# Main.net
KiCad netlist of a schematic drawn in Altium Designer
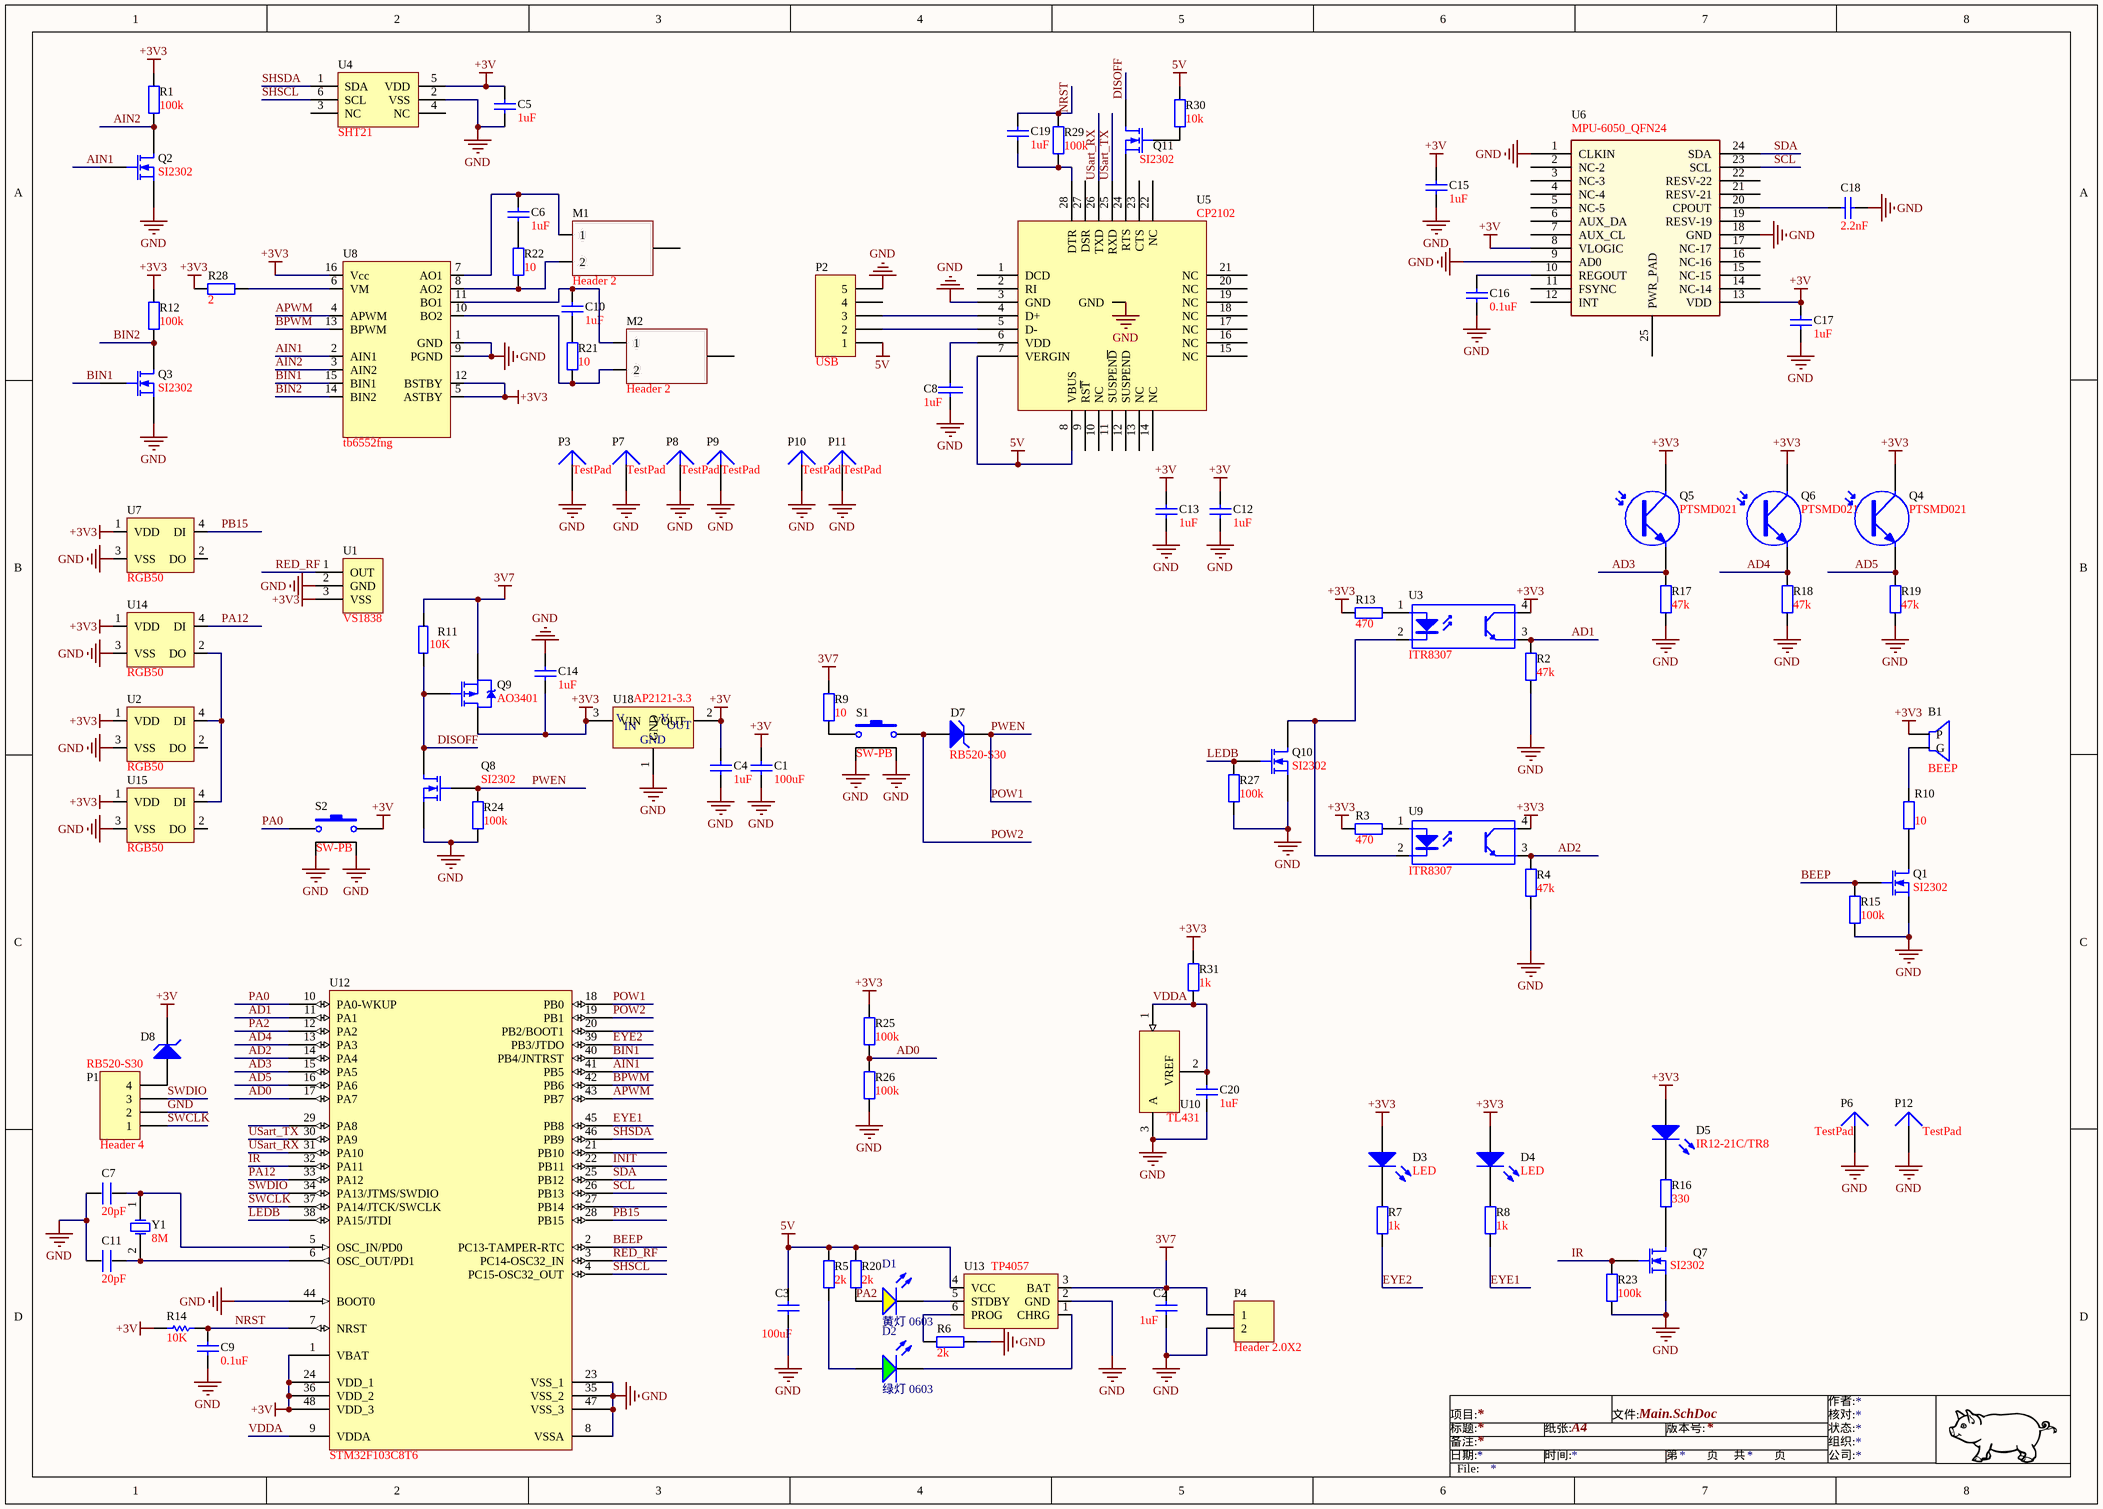
[diagram p0: Main.SchDoc]

(export (version "E")
  (design (tool "Eeschema 10.0.6"))
  (components
    (comp (ref "B1")
      (value "BEEP")
      (footprint "BEEP")
      (description "最小蜂鸣器6MM 6038 6035电磁式蜂鸣器 6*3.5 6*3.8MM 无源 交流")
      (libsource (lib "WARSHIP_SCH") (part "BEEP"))
    )
    (comp (ref "C1")
      (value "100uF")
      (footprint "3.5X2.8X1.9")
      (description "贴片电容")
      (fields (field (name "PUBLISHER") "Altium Limited"))
      (libsource (lib "Miscellaneous Devices") (part "Cap"))
    )
    (comp (ref "C2")
      (value "1uF")
      (footprint "C0603")
      (description "贴片电容")
      (fields (field (name "PUBLISHER") "Altium Limited"))
      (libsource (lib "Miscellaneous Devices") (part "Cap"))
    )
    (comp (ref "C3")
      (value "100uF")
      (footprint "3.5X2.8X1.9")
      (description "贴片电容")
      (fields (field (name "PUBLISHER") "Altium Limited"))
      (libsource (lib "Miscellaneous Devices") (part "Cap"))
    )
    (comp (ref "C4")
      (value "1uF")
      (footprint "C0603")
      (description "贴片电容")
      (fields (field (name "PUBLISHER") "Altium Limited"))
      (libsource (lib "Miscellaneous Devices") (part "Cap"))
    )
    (comp (ref "C5")
      (value "1uF")
      (footprint "c0603")
      (description "贴片电容")
      (fields (field (name "PUBLISHER") "Altium Limited"))
      (libsource (lib "Miscellaneous Devices") (part "Cap"))
    )
    (comp (ref "C6")
      (value "1uF")
      (footprint "c0603")
      (description "贴片电容")
      (fields (field (name "PUBLISHER") "Altium Limited"))
      (libsource (lib "Miscellaneous Devices") (part "Cap"))
    )
    (comp (ref "C7")
      (value "20pF")
      (footprint "C0603")
      (description "叠层贴片电容")
      (libsource (lib "WARSHIP_SCH") (part "C"))
    )
    (comp (ref "C8")
      (value "1uF")
      (footprint "C0603")
      (description "贴片电容")
      (libsource (lib "*") (part "CAP"))
    )
    (comp (ref "C9")
      (value "0.1uF")
      (footprint "C0603")
      (description "电容")
      (fields (field (name "PUBLISHER") "Altium Limited"))
      (libsource (lib "Main4") (part "CAP"))
    )
    (comp (ref "C10")
      (value "1uF")
      (footprint "c0603")
      (description "贴片电容")
      (fields (field (name "PUBLISHER") "Altium Limited"))
      (libsource (lib "Miscellaneous Devices") (part "Cap"))
    )
    (comp (ref "C11")
      (value "20pF")
      (footprint "C0603")
      (description "叠层贴片电容")
      (libsource (lib "WARSHIP_SCH") (part "C"))
    )
    (comp (ref "C12")
      (value "1uF")
      (footprint "C0603")
      (description "贴片电容")
      (fields (field (name "PUBLISHER") "Altium Limited"))
      (libsource (lib "Miscellaneous Devices") (part "Cap"))
    )
    (comp (ref "C13")
      (value "1uF")
      (footprint "C0603")
      (description "贴片电容")
      (fields (field (name "PUBLISHER") "Altium Limited"))
      (libsource (lib "Miscellaneous Devices") (part "Cap"))
    )
    (comp (ref "C14")
      (value "1uF")
      (footprint "C0603")
      (description "贴片电容")
      (fields (field (name "PUBLISHER") "Altium Limited"))
      (libsource (lib "Miscellaneous Devices") (part "Cap"))
    )
    (comp (ref "C15")
      (value "1uF")
      (footprint "C0603")
      (description "贴片电容")
      (fields (field (name "PUBLISHER") "Altium Limited"))
      (libsource (lib "Miscellaneous Devices") (part "Cap"))
    )
    (comp (ref "C16")
      (value "0.1uF")
      (footprint "C0603")
      (description "贴片电容")
      (fields (field (name "PUBLISHER") "Altium Limited"))
      (libsource (lib "Miscellaneous Devices") (part "Cap"))
    )
    (comp (ref "C17")
      (value "1uF")
      (footprint "C0603")
      (description "贴片电容")
      (fields (field (name "PUBLISHER") "Altium Limited"))
      (libsource (lib "Miscellaneous Devices") (part "Cap"))
    )
    (comp (ref "C18")
      (value "2.2nF")
      (footprint "C0603")
      (description "贴片电容")
      (fields (field (name "PUBLISHER") "Altium Limited"))
      (libsource (lib "Miscellaneous Devices") (part "Cap"))
    )
    (comp (ref "C19")
      (value "1uF")
      (footprint "c0603")
      (description "贴片电容")
      (fields (field (name "PUBLISHER") "Altium Limited"))
      (libsource (lib "Miscellaneous Devices") (part "Cap"))
    )
    (comp (ref "C20")
      (value "1uF")
      (footprint "C0603")
      (description "贴片电容")
      (fields (field (name "PUBLISHER") "Altium Limited"))
      (libsource (lib "Miscellaneous Devices") (part "Cap"))
    )
    (comp (ref "D1")
      (value "黄灯 0603")
      (footprint "0603_LED_S1")
      (description "发光二极管")
      (libsource (lib "Miscellaneous Devices LC") (part "0603 黄灯"))
    )
    (comp (ref "D2")
      (value "绿灯 0603")
      (footprint "0603_LED_S1")
      (description "发光二极管")
      (libsource (lib "Miscellaneous Devices LC") (part "0603 绿灯"))
    )
    (comp (ref "D3")
      (value "LED")
      (footprint "0802")
      (description "Typical RED, GREEN, YELLOW, AMBER GaAs LED")
      (fields (field (name "PUBLISHER") "Altium Limited"))
      (libsource (lib "Miscellaneous Devices") (part "LED0805"))
    )
    (comp (ref "D4")
      (value "LED")
      (footprint "0802")
      (description "Typical RED, GREEN, YELLOW, AMBER GaAs LED")
      (fields (field (name "PUBLISHER") "Altium Limited"))
      (libsource (lib "Miscellaneous Devices") (part "LED0805"))
    )
    (comp (ref "D5")
      (value "IR12-21C/TR8")
      (footprint "1206")
      (description "侧贴红外发射管")
      (fields (field (name "PUBLISHER") "Altium Limited"))
      (libsource (lib "Miscellaneous Devices") (part "LED0805"))
    )
    (comp (ref "D7")
      (value "RB520-S30")
      (footprint "LED")
      (description "肖基特二极管")
      (fields (field (name "PUBLISHER") "Altium Limited"))
      (libsource (lib "Miscellaneous Devices") (part "D Zener"))
    )
    (comp (ref "D8")
      (value "RB520-S30")
      (footprint "LED")
      (description "肖基特二极管")
      (fields (field (name "PUBLISHER") "Altium Limited"))
      (libsource (lib "Miscellaneous Devices") (part "D Zener"))
    )
    (comp (ref "M1")
      (value "Header 2")
      (footprint "PAD2")
      (description "Header, 2-Pin")
      (fields (field (name "PUBLISHER") "Altium Limited"))
      (libsource (lib "甲壳虫Geek-InSect_1") (part "Header 2"))
    )
    (comp (ref "M2")
      (value "Header 2")
      (footprint "PAD2")
      (description "Header, 2-Pin")
      (fields (field (name "PUBLISHER") "Altium Limited"))
      (libsource (lib "甲壳虫Geek-InSect_1") (part "Header 2"))
    )
    (comp (ref "P1")
      (value "Header 4")
      (footprint "SIP1.25-4")
      (description "Header, 4-Pin")
      (fields (field (name "PUBLISHER") "Altium Limited"))
      (libsource (lib "Miscellaneous Connectors") (part "Header 4"))
    )
    (comp (ref "P2")
      (value "USB")
      (footprint "MICROUSB4")
      (description "迈克USB 接口 4个固定脚插板固定母座-5p贴片长针 MICRO usb接口 [交易快照]")
      (fields (field (name "PUBLISHER") "Altium Limited"))
      (libsource (lib "Miscellaneous Connectors") (part "Header 5"))
    )
    (comp (ref "P3")
      (value "TestPad")
      (footprint "MOTO")
      (description "Plug")
      (fields (field (name "PUBLISHER") "Altium Limited"))
      (libsource (lib "Miscellaneous Connectors") (part "Plug"))
    )
    (comp (ref "P4")
      (value "Header 2.0X2")
      (footprint "Head2.0")
      (description "2.0dip连接器")
      (fields (field (name "PUBLISHER") "Altium Limited"))
      (libsource (lib "Miscellaneous Connectors") (part "Header 2"))
    )
    (comp (ref "P6")
      (value "TestPad")
      (footprint "PAD")
      (description "Plug")
      (fields (field (name "PUBLISHER") "Altium Limited"))
      (libsource (lib "Miscellaneous Connectors") (part "Plug"))
    )
    (comp (ref "P7")
      (value "TestPad")
      (footprint "MOTO")
      (description "Plug")
      (fields (field (name "PUBLISHER") "Altium Limited"))
      (libsource (lib "Miscellaneous Connectors") (part "Plug"))
    )
    (comp (ref "P8")
      (value "TestPad")
      (footprint "PAD")
      (description "Plug")
      (fields (field (name "PUBLISHER") "Altium Limited"))
      (libsource (lib "Miscellaneous Connectors") (part "Plug"))
    )
    (comp (ref "P9")
      (value "TestPad")
      (footprint "PAD")
      (description "Plug")
      (fields (field (name "PUBLISHER") "Altium Limited"))
      (libsource (lib "Miscellaneous Connectors") (part "Plug"))
    )
    (comp (ref "P10")
      (value "TestPad")
      (footprint "PAD")
      (description "Plug")
      (fields (field (name "PUBLISHER") "Altium Limited"))
      (libsource (lib "Miscellaneous Connectors") (part "Plug"))
    )
    (comp (ref "P11")
      (value "TestPad")
      (footprint "PAD")
      (description "Plug")
      (fields (field (name "PUBLISHER") "Altium Limited"))
      (libsource (lib "Miscellaneous Connectors") (part "Plug"))
    )
    (comp (ref "P12")
      (value "TestPad")
      (footprint "PAD")
      (description "Plug")
      (fields (field (name "PUBLISHER") "Altium Limited"))
      (libsource (lib "Miscellaneous Connectors") (part "Plug"))
    )
    (comp (ref "Q1")
      (value "SI2302")
      (footprint "SOT-23_L")
      (description "N-Channel MOSFET")
      (fields (field (name "PUBLISHER") "Altium Limited"))
      (libsource (lib "Miscellaneous Devices") (part "MOSFET-N"))
    )
    (comp (ref "Q2")
      (value "SI2302")
      (footprint "SOT-23_L")
      (description "N-Channel MOSFET")
      (fields (field (name "PUBLISHER") "Altium Limited"))
      (libsource (lib "Miscellaneous Devices") (part "MOSFET-N"))
    )
    (comp (ref "Q3")
      (value "SI2302")
      (footprint "SOT-23_L")
      (description "N-Channel MOSFET")
      (fields (field (name "PUBLISHER") "Altium Limited"))
      (libsource (lib "Miscellaneous Devices") (part "MOSFET-N"))
    )
    (comp (ref "Q4")
      (value "PTSMD021")
      (footprint "EYE")
      (description "光线传感器")
      (fields (field (name "PUBLISHER") "Altium Limited"))
      (libsource (lib "Miscellaneous Devices") (part "Photo NPN"))
    )
    (comp (ref "Q5")
      (value "PTSMD021")
      (footprint "EYE")
      (description "光线传感器")
      (fields (field (name "PUBLISHER") "Altium Limited"))
      (libsource (lib "Miscellaneous Devices") (part "Photo NPN"))
    )
    (comp (ref "Q6")
      (value "PTSMD021")
      (footprint "EYE")
      (description "光线传感器")
      (fields (field (name "PUBLISHER") "Altium Limited"))
      (libsource (lib "Miscellaneous Devices") (part "Photo NPN"))
    )
    (comp (ref "Q7")
      (value "SI2302")
      (footprint "SOT-23_L")
      (description "N-Channel MOSFET")
      (fields (field (name "PUBLISHER") "Altium Limited"))
      (libsource (lib "Miscellaneous Devices") (part "MOSFET-N"))
    )
    (comp (ref "Q8")
      (value "SI2302")
      (footprint "SOT-23_L")
      (description "N-Channel MOSFET")
      (fields (field (name "PUBLISHER") "Altium Limited"))
      (libsource (lib "Miscellaneous Devices") (part "MOSFET-N"))
    )
    (comp (ref "Q9")
      (value "AO3401")
      (footprint "SOT23_L")
      (description "P沟道电源开关MOS管")
      (fields (field (name "PUBLISHER") "Altium Limited"))
      (libsource (lib "Miscellaneous Devices") (part "PMOS-2"))
    )
    (comp (ref "Q10")
      (value "SI2302")
      (footprint "SOT-23_L")
      (description "N-Channel MOSFET")
      (fields (field (name "PUBLISHER") "Altium Limited"))
      (libsource (lib "Miscellaneous Devices") (part "MOSFET-N"))
    )
    (comp (ref "Q11")
      (value "SI2302")
      (footprint "SOT-23_L")
      (description "N-Channel MOSFET")
      (fields (field (name "PUBLISHER") "Altium Limited"))
      (libsource (lib "Miscellaneous Devices") (part "MOSFET-N"))
    )
    (comp (ref "R1")
      (value "100k")
      (footprint "R0603")
      (description "贴片电阻")
      (fields (field (name "PUBLISHER") "Altium Limited"))
      (libsource (lib "Miscellaneous Devices") (part "Res2"))
    )
    (comp (ref "R2")
      (value "47k")
      (footprint "R0603")
      (description "贴片电阻")
      (fields (field (name "PUBLISHER") "Altium Limited"))
      (libsource (lib "Miscellaneous Devices") (part "Res2"))
    )
    (comp (ref "R3")
      (value "470")
      (footprint "R0603")
      (description "贴片电阻")
      (fields (field (name "PUBLISHER") "Altium Limited"))
      (libsource (lib "") (part "Res2_2"))
    )
    (comp (ref "R4")
      (value "47k")
      (footprint "R0603")
      (description "贴片电阻")
      (fields (field (name "PUBLISHER") "Altium Limited"))
      (libsource (lib "Miscellaneous Devices") (part "Res2"))
    )
    (comp (ref "R5")
      (value "2k")
      (footprint "R0603")
      (description "贴片电阻")
      (fields (field (name "PUBLISHER") "Altium Limited"))
      (libsource (lib "Miscellaneous Devices") (part "=Value"))
    )
    (comp (ref "R6")
      (value "2k")
      (footprint "R0603")
      (description "贴片电阻")
      (fields (field (name "PUBLISHER") "Altium Limited"))
      (libsource (lib "") (part "=Value_1"))
    )
    (comp (ref "R7")
      (value "1k")
      (footprint "R0603")
      (description "贴片电阻")
      (fields (field (name "PUBLISHER") "Altium Limited"))
      (libsource (lib "Miscellaneous Devices") (part "Res2"))
    )
    (comp (ref "R8")
      (value "1k")
      (footprint "R0603")
      (description "贴片电阻")
      (fields (field (name "PUBLISHER") "Altium Limited"))
      (libsource (lib "Miscellaneous Devices") (part "Res2"))
    )
    (comp (ref "R9")
      (value "10")
      (footprint "R0603")
      (description "贴片电阻")
      (fields (field (name "PUBLISHER") "Altium Limited"))
      (libsource (lib "Miscellaneous Devices") (part "Res2"))
    )
    (comp (ref "R10")
      (value "10")
      (footprint "R0603")
      (description "贴片电阻")
      (fields (field (name "PUBLISHER") "Altium Limited"))
      (libsource (lib "Miscellaneous Devices") (part "Res2"))
    )
    (comp (ref "R11")
      (value "10K")
      (footprint "R0603")
      (description "贴片电阻")
      (libsource (lib "WARSHIP_SCH") (part "R"))
    )
    (comp (ref "R12")
      (value "100k")
      (footprint "R0603")
      (description "贴片电阻")
      (fields (field (name "PUBLISHER") "Altium Limited"))
      (libsource (lib "Miscellaneous Devices") (part "Res2"))
    )
    (comp (ref "R13")
      (value "470")
      (footprint "R0603")
      (description "贴片电阻")
      (fields (field (name "PUBLISHER") "Altium Limited"))
      (libsource (lib "") (part "Res2_2"))
    )
    (comp (ref "R14")
      (value "10K")
      (footprint "R0603")
      (description "电阻")
      (fields (field (name "PUBLISHER") "Altium Limited"))
      (libsource (lib "Main4") (part "res1"))
    )
    (comp (ref "R15")
      (value "100k")
      (footprint "R0603")
      (description "贴片电阻")
      (fields (field (name "PUBLISHER") "Altium Limited"))
      (libsource (lib "Miscellaneous Devices") (part "Res2"))
    )
    (comp (ref "R16")
      (value "330")
      (footprint "R0603")
      (description "贴片电阻")
      (fields (field (name "PUBLISHER") "Altium Limited"))
      (libsource (lib "Miscellaneous Devices") (part "Res2"))
    )
    (comp (ref "R17")
      (value "47k")
      (footprint "R0603")
      (description "贴片电阻")
      (fields (field (name "PUBLISHER") "Altium Limited"))
      (libsource (lib "") (part "Res2_1"))
    )
    (comp (ref "R18")
      (value "47k")
      (footprint "R0603")
      (description "贴片电阻")
      (fields (field (name "PUBLISHER") "Altium Limited"))
      (libsource (lib "") (part "Res2_1"))
    )
    (comp (ref "R19")
      (value "47k")
      (footprint "R0603")
      (description "贴片电阻")
      (fields (field (name "PUBLISHER") "Altium Limited"))
      (libsource (lib "") (part "Res2_1"))
    )
    (comp (ref "R20")
      (value "2k")
      (footprint "R0603")
      (description "贴片电阻")
      (fields (field (name "PUBLISHER") "Altium Limited"))
      (libsource (lib "Miscellaneous Devices") (part "=Value"))
    )
    (comp (ref "R21")
      (value "10")
      (footprint "R0603")
      (description "贴片电阻")
      (fields (field (name "PUBLISHER") "Altium Limited"))
      (libsource (lib "Miscellaneous Devices") (part "Res2"))
    )
    (comp (ref "R22")
      (value "10")
      (footprint "R0603")
      (description "贴片电阻")
      (fields (field (name "PUBLISHER") "Altium Limited"))
      (libsource (lib "Miscellaneous Devices") (part "Res2"))
    )
    (comp (ref "R23")
      (value "100k")
      (footprint "R0603")
      (description "贴片电阻")
      (fields (field (name "PUBLISHER") "Altium Limited"))
      (libsource (lib "Miscellaneous Devices") (part "Res2"))
    )
    (comp (ref "R24")
      (value "100k")
      (footprint "R0603")
      (description "贴片电阻")
      (fields (field (name "PUBLISHER") "Altium Limited"))
      (libsource (lib "") (part "Res2_2"))
    )
    (comp (ref "R25")
      (value "100k")
      (footprint "R0603")
      (description "贴片电阻")
      (fields (field (name "PUBLISHER") "Altium Limited"))
      (libsource (lib "Miscellaneous Devices") (part "Res2"))
    )
    (comp (ref "R26")
      (value "100k")
      (footprint "R0603")
      (description "贴片电阻")
      (fields (field (name "PUBLISHER") "Altium Limited"))
      (libsource (lib "Miscellaneous Devices") (part "Res2"))
    )
    (comp (ref "R27")
      (value "100k")
      (footprint "R0603")
      (description "贴片电阻")
      (fields (field (name "PUBLISHER") "Altium Limited"))
      (libsource (lib "Miscellaneous Devices") (part "Res2"))
    )
    (comp (ref "R28")
      (value "2")
      (footprint "R0603")
      (description "贴片电阻")
      (fields (field (name "PUBLISHER") "Altium Limited"))
      (libsource (lib "") (part "Res2_3"))
    )
    (comp (ref "R29")
      (value "100k")
      (footprint "R0603")
      (description "贴片电阻")
      (fields (field (name "PUBLISHER") "Altium Limited"))
      (libsource (lib "Miscellaneous Devices") (part "Res2"))
    )
    (comp (ref "R30")
      (value "10k")
      (footprint "R0603")
      (description "贴片电阻")
      (fields (field (name "PUBLISHER") "Altium Limited"))
      (libsource (lib "Miscellaneous Devices") (part "Res2"))
    )
    (comp (ref "R31")
      (value "1k")
      (footprint "R0603")
      (description "贴片电阻")
      (fields (field (name "PUBLISHER") "Altium Limited"))
      (libsource (lib "Miscellaneous Devices") (part "Res2"))
    )
    (comp (ref "S1")
      (value "SW-PB")
      (footprint "BUTTON")
      (description "3x6x3.5H 3*6*3.5贴片 侧位 按钮")
      (fields (field (name "PUBLISHER") "Altium Limited"))
      (libsource (lib "甲壳虫Geek-InSect_1") (part "SW-PB"))
    )
    (comp (ref "S2")
      (value "SW-PB")
      (footprint "BUTTON")
      (description "3x6x3.5H 3*6*3.5贴片 侧位 按钮")
      (fields (field (name "PUBLISHER") "Altium Limited"))
      (libsource (lib "甲壳虫Geek-InSect_1") (part "SW-PB"))
    )
    (comp (ref "U1")
      (value "VS1838")
      (footprint "IR38")
      (description "1838 接收头 VS1838 VS1838B")
      (libsource (lib "甲壳虫Geek-InSect_1") (part "RF"))
    )
    (comp (ref "U2")
      (value "RGB50")
      (footprint "HV-EYE - duplicate")
      (description "全彩REG灯珠PCB附件")
      (libsource (lib "甲壳虫Geek-InSect") (part "RGB50"))
    )
    (comp (ref "U3")
      (value "ITR8307")
      (footprint "ITR8307")
      (description "反射式光学传感器")
      (fields (field (name "PUBLISHER") "Altium Limited"))
      (libsource (lib "甲壳虫Geek-InSect") (part "Optoisolator1"))
    )
    (comp (ref "U4")
      (value "SHT21")
      (footprint "SHT20")
      (description "温湿度探头(缺省)")
      (libsource (lib "*") (part "SHT21"))
    )
    (comp (ref "U5")
      (value "CP2102")
      (footprint "qfn-28")
      (description "usb  转ttl")
      (libsource (lib "甲壳虫Geek-InSect_1") (part "CP2102"))
    )
    (comp (ref "U6")
      (value "MPU-6050_QFN24")
      (footprint "qfn24")
      (description "三轴陀螺仪加速度")
      (libsource (lib "*") (part "MPU06050_QFN24"))
    )
    (comp (ref "U7")
      (value "RGB50")
      (footprint "WS2812")
      (description "WS2812全彩RGB灯珠")
      (libsource (lib "甲壳虫Geek-InSect") (part "RGB50"))
    )
    (comp (ref "U8")
      (value "tb6552fng")
      (footprint "SSOP16_L")
      (description "电机驱动芯片")
      (libsource (lib "甲壳虫Geek-InSect") (part "tb6552fng"))
    )
    (comp (ref "U9")
      (value "ITR8307")
      (footprint "ITR8307")
      (description "反射式光学传感器")
      (fields (field (name "PUBLISHER") "Altium Limited"))
      (libsource (lib "甲壳虫Geek-InSect") (part "Optoisolator1"))
    )
    (comp (ref "U10")
      (value "TL431")
      (footprint "SOT-23_L")
      (description "TL431BID")
      (fields
        (field (name "MANUFACTURER") "Texas Instruments")
        (field (name "PUBLISHER") "Altium Hobart Technology Centre")
      )
      (libsource (lib "TI Power Mgt Voltage Regulator") (part "TL431AILP"))
    )
    (comp (ref "U12")
      (value "STM32F103C8T6")
      (footprint "LQFP48_N")
      (description "处理器")
      (fields (field (name "PUBLISHER") "*"))
      (libsource (lib "STM32_SCH") (part "STM32F103C8T6"))
    )
    (comp (ref "U13")
      (value "TP4057")
      (footprint "SOT23-6_N")
      (description "6pin  充电芯片  sot23-6")
      (libsource (lib "Nrf") (part "TP4057"))
    )
    (comp (ref "U14")
      (value "RGB50")
      (footprint "WS2812")
      (description "WS2812全彩RGB灯珠")
      (libsource (lib "甲壳虫Geek-InSect") (part "RGB50"))
    )
    (comp (ref "U15")
      (value "RGB50")
      (footprint "HV-EYE - duplicate")
      (description "全彩REG灯珠PCB附件")
      (libsource (lib "甲壳虫Geek-InSect") (part "RGB50"))
    )
    (comp (ref "U18")
      (value "AP2121-3.3")
      (footprint "SOT-23")
      (description "3V LDO")
      (libsource (lib "wllibs") (part "AP2121-3"))
    )
    (comp (ref "Y1")
      (value "8M")
      (footprint "16mhz")
      (description "cstce8m00g52")
      (libsource (lib "TP401G") (part "XTAL"))
    )
  )
  (nets
    (net (code "1") (name "+3V") (class "Default")
      (node (ref "C1") (pin "2") (pinfunction "2_2") (pintype "passive"))
      (node (ref "C12") (pin "1") (pinfunction "1_1") (pintype "passive"))
      (node (ref "C13") (pin "1") (pinfunction "1_1") (pintype "passive"))
      (node (ref "C15") (pin "1") (pinfunction "1_1") (pintype "passive"))
      (node (ref "C17") (pin "1") (pinfunction "1_1") (pintype "passive"))
      (node (ref "C4") (pin "1") (pinfunction "1_1") (pintype "passive"))
      (node (ref "C5") (pin "1") (pinfunction "1_1") (pintype "passive"))
      (node (ref "D8") (pin "2") (pinfunction "K_2") (pintype "passive"))
      (node (ref "R14") (pin "2") (pinfunction "2_2") (pintype "passive"))
      (node (ref "S2") (pin "1") (pinfunction "1_1") (pintype "passive"))
      (node (ref "U12") (pin "1") (pinfunction "VBAT_1") (pintype "power_in"))
      (node (ref "U12") (pin "24") (pinfunction "VDD_1_24") (pintype "power_in"))
      (node (ref "U12") (pin "36") (pinfunction "VDD_2_36") (pintype "power_in"))
      (node (ref "U12") (pin "48") (pinfunction "VDD_3_48") (pintype "power_in"))
      (node (ref "U18") (pin "2") (pinfunction "VOUT_2") (pintype "passive"))
      (node (ref "U4") (pin "5") (pinfunction "VDD_5") (pintype "passive"))
      (node (ref "U6") (pin "13") (pinfunction "VDD_13") (pintype "passive"))
      (node (ref "U6") (pin "8") (pinfunction "VLOGIC_8") (pintype "passive"))
    )
    (net (code "2") (name "+3V3") (class "Default")
      (node (ref "B1") (pin "1") (pinfunction "P_1") (pintype "passive"))
      (node (ref "C14") (pin "2") (pinfunction "2_2") (pintype "passive"))
      (node (ref "D3") (pin "1") (pinfunction "A_1") (pintype "passive"))
      (node (ref "D4") (pin "1") (pinfunction "A_1") (pintype "passive"))
      (node (ref "D5") (pin "1") (pinfunction "A_1") (pintype "passive"))
      (node (ref "Q4") (pin "1") (pinfunction "C_1") (pintype "passive"))
      (node (ref "Q5") (pin "1") (pinfunction "C_1") (pintype "passive"))
      (node (ref "Q6") (pin "1") (pinfunction "C_1") (pintype "passive"))
      (node (ref "Q9") (pin "2") (pinfunction "D_2") (pintype "passive"))
      (node (ref "R1") (pin "2") (pinfunction "2_2") (pintype "passive"))
      (node (ref "R12") (pin "2") (pinfunction "2_2") (pintype "passive"))
      (node (ref "R13") (pin "1") (pinfunction "1_1") (pintype "passive"))
      (node (ref "R25") (pin "2") (pinfunction "2_2") (pintype "passive"))
      (node (ref "R28") (pin "2") (pinfunction "2_2") (pintype "passive"))
      (node (ref "R3") (pin "1") (pinfunction "1_1") (pintype "passive"))
      (node (ref "R31") (pin "2") (pinfunction "2_2") (pintype "passive"))
      (node (ref "U1") (pin "3") (pinfunction "VSS_3") (pintype "passive"))
      (node (ref "U14") (pin "1") (pinfunction "VDD_1") (pintype "passive"))
      (node (ref "U15") (pin "1") (pinfunction "VDD_1") (pintype "passive"))
      (node (ref "U18") (pin "3") (pinfunction "VIN_3") (pintype "passive"))
      (node (ref "U2") (pin "1") (pinfunction "VDD_1") (pintype "passive"))
      (node (ref "U3") (pin "4") (pinfunction "C_4") (pintype "passive"))
      (node (ref "U7") (pin "1") (pinfunction "VDD_1") (pintype "passive"))
      (node (ref "U8") (pin "12") (pinfunction "BSTBY_12") (pintype "passive"))
      (node (ref "U8") (pin "16") (pinfunction "Vcc_16") (pintype "passive"))
      (node (ref "U8") (pin "5") (pinfunction "ASTBY_5") (pintype "passive"))
      (node (ref "U9") (pin "4") (pinfunction "C_4") (pintype "passive"))
    )
    (net (code "3") (name "/AD0") (class "Default")
      (node (ref "R25") (pin "1") (pinfunction "1_1") (pintype "passive"))
      (node (ref "R26") (pin "2") (pinfunction "2_2") (pintype "passive"))
      (node (ref "U12") (pin "17") (pinfunction "PA7_17") (pintype "bidirectional"))
    )
    (net (code "4") (name "/AD1") (class "Default")
      (node (ref "R2") (pin "2") (pinfunction "2_2") (pintype "passive"))
      (node (ref "U12") (pin "11") (pinfunction "PA1_11") (pintype "bidirectional"))
      (node (ref "U3") (pin "3") (pinfunction "E_3") (pintype "passive"))
    )
    (net (code "5") (name "/AD2") (class "Default")
      (node (ref "R4") (pin "2") (pinfunction "2_2") (pintype "passive"))
      (node (ref "U12") (pin "14") (pinfunction "PA4_14") (pintype "bidirectional"))
      (node (ref "U9") (pin "3") (pinfunction "E_3") (pintype "passive"))
    )
    (net (code "6") (name "/AD3") (class "Default")
      (node (ref "Q5") (pin "2") (pinfunction "E_2") (pintype "passive"))
      (node (ref "R17") (pin "1") (pinfunction "1_1") (pintype "passive"))
      (node (ref "U12") (pin "15") (pinfunction "PA5_15") (pintype "bidirectional"))
    )
    (net (code "7") (name "/AD4") (class "Default")
      (node (ref "Q6") (pin "2") (pinfunction "E_2") (pintype "passive"))
      (node (ref "R18") (pin "1") (pinfunction "1_1") (pintype "passive"))
      (node (ref "U12") (pin "13") (pinfunction "PA3_13") (pintype "bidirectional"))
    )
    (net (code "8") (name "/AD5") (class "Default")
      (node (ref "Q4") (pin "2") (pinfunction "E_2") (pintype "passive"))
      (node (ref "R19") (pin "1") (pinfunction "1_1") (pintype "passive"))
      (node (ref "U12") (pin "16") (pinfunction "PA6_16") (pintype "bidirectional"))
    )
    (net (code "9") (name "/AIN1") (class "Default")
      (node (ref "Q2") (pin "2") (pinfunction "G_2") (pintype "passive"))
      (node (ref "U12") (pin "41") (pinfunction "PB5_41") (pintype "bidirectional"))
      (node (ref "U8") (pin "2") (pinfunction "AIN1_2") (pintype "passive"))
    )
    (net (code "10") (name "/AIN2") (class "Default")
      (node (ref "Q2") (pin "1") (pinfunction "D_1") (pintype "passive"))
      (node (ref "R1") (pin "1") (pinfunction "1_1") (pintype "passive"))
      (node (ref "U8") (pin "3") (pinfunction "AIN2_3") (pintype "passive"))
    )
    (net (code "11") (name "/APWM") (class "Default")
      (node (ref "U12") (pin "43") (pinfunction "PB7_43") (pintype "bidirectional"))
      (node (ref "U8") (pin "4") (pinfunction "APWM_4") (pintype "passive"))
    )
    (net (code "12") (name "/BEEP") (class "Default")
      (node (ref "Q1") (pin "2") (pinfunction "G_2") (pintype "passive"))
      (node (ref "R15") (pin "2") (pinfunction "2_2") (pintype "passive"))
      (node (ref "U12") (pin "2") (pinfunction "PC13-TAMPER-RTC_2") (pintype "bidirectional"))
    )
    (net (code "13") (name "/BIN1") (class "Default")
      (node (ref "Q3") (pin "2") (pinfunction "G_2") (pintype "passive"))
      (node (ref "U12") (pin "40") (pinfunction "PB4/JNTRST_40") (pintype "bidirectional"))
      (node (ref "U8") (pin "15") (pinfunction "BIN1_15") (pintype "passive"))
    )
    (net (code "14") (name "/BIN2") (class "Default")
      (node (ref "Q3") (pin "1") (pinfunction "D_1") (pintype "passive"))
      (node (ref "R12") (pin "1") (pinfunction "1_1") (pintype "passive"))
      (node (ref "U8") (pin "14") (pinfunction "BIN2_14") (pintype "passive"))
    )
    (net (code "15") (name "/BPWM") (class "Default")
      (node (ref "U12") (pin "42") (pinfunction "PB6_42") (pintype "bidirectional"))
      (node (ref "U8") (pin "13") (pinfunction "BPWM_13") (pintype "passive"))
    )
    (net (code "16") (name "/DISOFF") (class "Default")
      (node (ref "Q11") (pin "1") (pinfunction "D_1") (pintype "passive"))
      (node (ref "Q8") (pin "1") (pinfunction "D_1") (pintype "passive"))
      (node (ref "Q9") (pin "1") (pinfunction "G_1") (pintype "passive"))
      (node (ref "R11") (pin "1") (pintype "passive"))
    )
    (net (code "17") (name "/EYE1") (class "Default")
      (node (ref "R8") (pin "1") (pinfunction "1_1") (pintype "passive"))
      (node (ref "U12") (pin "45") (pinfunction "PB8_45") (pintype "bidirectional"))
    )
    (net (code "18") (name "/EYE2") (class "Default")
      (node (ref "R7") (pin "1") (pinfunction "1_1") (pintype "passive"))
      (node (ref "U12") (pin "39") (pinfunction "PB3/JTDO_39") (pintype "bidirectional"))
    )
    (net (code "19") (name "/INIT") (class "Default")
      (node (ref "U12") (pin "22") (pinfunction "PB11_22") (pintype "bidirectional"))
    )
    (net (code "20") (name "/IR") (class "Default")
      (node (ref "Q7") (pin "2") (pinfunction "G_2") (pintype "passive"))
      (node (ref "R23") (pin "2") (pinfunction "2_2") (pintype "passive"))
      (node (ref "U12") (pin "32") (pinfunction "PA11_32") (pintype "bidirectional"))
    )
    (net (code "21") (name "/LEDB") (class "Default")
      (node (ref "Q10") (pin "2") (pinfunction "G_2") (pintype "passive"))
      (node (ref "R27") (pin "2") (pinfunction "2_2") (pintype "passive"))
      (node (ref "U12") (pin "38") (pinfunction "PA15/JTDI_38") (pintype "bidirectional"))
    )
    (net (code "22") (name "/NRST") (class "Default")
      (node (ref "C19") (pin "1") (pinfunction "1_1") (pintype "passive"))
      (node (ref "C9") (pin "2") (pinfunction "2_2") (pintype "passive"))
      (node (ref "R14") (pin "1") (pinfunction "1_1") (pintype "passive"))
      (node (ref "R29") (pin "2") (pinfunction "2_2") (pintype "passive"))
      (node (ref "U12") (pin "7") (pinfunction "NRST_7") (pintype "bidirectional"))
    )
    (net (code "23") (name "/PA0") (class "Default")
      (node (ref "S2") (pin "2") (pinfunction "2_2") (pintype "passive"))
      (node (ref "U12") (pin "10") (pinfunction "PA0-WKUP_10") (pintype "bidirectional"))
    )
    (net (code "24") (name "/PA2") (class "Default")
      (node (ref "D1") (pin "A") (pinfunction "A_A") (pintype "passive"))
      (node (ref "R20") (pin "1") (pinfunction "1_1") (pintype "passive"))
      (node (ref "U12") (pin "12") (pinfunction "PA2_12") (pintype "bidirectional"))
    )
    (net (code "25") (name "/PA12") (class "Default")
      (node (ref "U12") (pin "33") (pinfunction "PA12_33") (pintype "bidirectional"))
      (node (ref "U14") (pin "4") (pinfunction "DI_4") (pintype "passive"))
    )
    (net (code "26") (name "/PB15") (class "Default")
      (node (ref "U12") (pin "28") (pinfunction "PB15_28") (pintype "bidirectional"))
      (node (ref "U7") (pin "4") (pinfunction "DI_4") (pintype "passive"))
    )
    (net (code "27") (name "/POW1") (class "Default")
      (node (ref "D7") (pin "2") (pinfunction "K_2") (pintype "passive"))
      (node (ref "Q8") (pin "2") (pinfunction "G_2") (pintype "passive"))
      (node (ref "R24") (pin "2") (pinfunction "2_2") (pintype "passive"))
      (node (ref "U12") (pin "18") (pinfunction "PB0_18") (pintype "bidirectional"))
    )
    (net (code "28") (name "/POW2") (class "Default")
      (node (ref "D7") (pin "1") (pinfunction "A_1") (pintype "passive"))
      (node (ref "S1") (pin "2") (pinfunction "2_2") (pintype "passive"))
      (node (ref "U12") (pin "19") (pinfunction "PB1_19") (pintype "bidirectional"))
    )
    (net (code "29") (name "/RED_RF") (class "Default")
      (node (ref "U1") (pin "1") (pinfunction "OUT_1") (pintype "passive"))
      (node (ref "U12") (pin "3") (pinfunction "PC14-OSC32_IN_3") (pintype "bidirectional"))
    )
    (net (code "30") (name "/SCL") (class "Default")
      (node (ref "U12") (pin "26") (pinfunction "PB13_26") (pintype "bidirectional"))
      (node (ref "U6") (pin "23") (pinfunction "SCL_23") (pintype "passive"))
    )
    (net (code "31") (name "/SDA") (class "Default")
      (node (ref "U12") (pin "25") (pinfunction "PB12_25") (pintype "bidirectional"))
      (node (ref "U6") (pin "24") (pinfunction "SDA_24") (pintype "passive"))
    )
    (net (code "32") (name "/SHSCL") (class "Default")
      (node (ref "U12") (pin "4") (pinfunction "PC15-OSC32_OUT_4") (pintype "bidirectional"))
      (node (ref "U4") (pin "6") (pinfunction "SCL_6") (pintype "passive"))
    )
    (net (code "33") (name "/SHSDA") (class "Default")
      (node (ref "U12") (pin "46") (pinfunction "PB9_46") (pintype "bidirectional"))
      (node (ref "U4") (pin "1") (pinfunction "SDA_1") (pintype "passive"))
    )
    (net (code "34") (name "/SWCLK") (class "Default")
      (node (ref "P1") (pin "1") (pinfunction "1_1") (pintype "passive"))
      (node (ref "U12") (pin "37") (pinfunction "PA14/JTCK/SWCLK_37") (pintype "bidirectional"))
    )
    (net (code "35") (name "/SWDIO") (class "Default")
      (node (ref "P1") (pin "3") (pinfunction "3_3") (pintype "passive"))
      (node (ref "U12") (pin "34") (pinfunction "PA13/JTMS/SWDIO_34") (pintype "bidirectional"))
    )
    (net (code "36") (name "/USart_RX") (class "Default")
      (node (ref "U12") (pin "31") (pinfunction "PA10_31") (pintype "bidirectional"))
      (node (ref "U5") (pin "26") (pinfunction "TXD_26") (pintype "passive"))
    )
    (net (code "37") (name "/USart_TX") (class "Default")
      (node (ref "U12") (pin "30") (pinfunction "PA9_30") (pintype "bidirectional"))
      (node (ref "U5") (pin "25") (pinfunction "RXD_25") (pintype "passive"))
    )
    (net (code "38") (name "/VDDA") (class "Default")
      (node (ref "C20") (pin "1") (pinfunction "1_1") (pintype "passive"))
      (node (ref "R31") (pin "1") (pinfunction "1_1") (pintype "passive"))
      (node (ref "U10") (pin "1") (pinfunction "K_1") (pintype "input"))
      (node (ref "U10") (pin "2") (pintype "power_in"))
      (node (ref "U12") (pin "9") (pinfunction "VDDA_9") (pintype "power_in"))
    )
    (net (code "39") (name "3V7") (class "Default")
      (node (ref "C2") (pin "2") (pinfunction "2_2") (pintype "passive"))
      (node (ref "P4") (pin "1") (pinfunction "1_1") (pintype "passive"))
      (node (ref "Q9") (pin "3") (pinfunction "S_3") (pintype "passive"))
      (node (ref "R11") (pin "2") (pintype "passive"))
      (node (ref "R9") (pin "2") (pinfunction "2_2") (pintype "passive"))
      (node (ref "U13") (pin "3") (pinfunction "BAT_3") (pintype "passive"))
    )
    (net (code "40") (name "5V") (class "Default")
      (node (ref "C3") (pin "2") (pinfunction "2_2") (pintype "passive"))
      (node (ref "P2") (pin "1") (pinfunction "1_1") (pintype "passive"))
      (node (ref "R20") (pin "2") (pinfunction "2_2") (pintype "passive"))
      (node (ref "R30") (pin "2") (pinfunction "2_2") (pintype "passive"))
      (node (ref "R5") (pin "2") (pinfunction "2_2") (pintype "passive"))
      (node (ref "U13") (pin "4") (pinfunction "VCC_4") (pintype "passive"))
      (node (ref "U5") (pin "7") (pinfunction "VERGIN_7") (pintype "passive"))
      (node (ref "U5") (pin "8") (pinfunction "VBUS_8") (pintype "passive"))
    )
    (net (code "41") (name "GND") (class "Default")
      (node (ref "C1") (pin "1") (pinfunction "1_1") (pintype "passive"))
      (node (ref "C11") (pin "1") (pintype "passive"))
      (node (ref "C12") (pin "2") (pinfunction "2_2") (pintype "passive"))
      (node (ref "C13") (pin "2") (pinfunction "2_2") (pintype "passive"))
      (node (ref "C14") (pin "1") (pinfunction "1_1") (pintype "passive"))
      (node (ref "C15") (pin "2") (pinfunction "2_2") (pintype "passive"))
      (node (ref "C16") (pin "2") (pinfunction "2_2") (pintype "passive"))
      (node (ref "C17") (pin "2") (pinfunction "2_2") (pintype "passive"))
      (node (ref "C18") (pin "2") (pinfunction "2_2") (pintype "passive"))
      (node (ref "C2") (pin "1") (pinfunction "1_1") (pintype "passive"))
      (node (ref "C20") (pin "2") (pinfunction "2_2") (pintype "passive"))
      (node (ref "C3") (pin "1") (pinfunction "1_1") (pintype "passive"))
      (node (ref "C4") (pin "2") (pinfunction "2_2") (pintype "passive"))
      (node (ref "C5") (pin "2") (pinfunction "2_2") (pintype "passive"))
      (node (ref "C7") (pin "1") (pintype "passive"))
      (node (ref "C8") (pin "1") (pinfunction "1_1") (pintype "passive"))
      (node (ref "C9") (pin "1") (pinfunction "1_1") (pintype "passive"))
      (node (ref "P1") (pin "2") (pinfunction "2_2") (pintype "passive"))
      (node (ref "P10") (pin "1") (pinfunction "1_1") (pintype "passive"))
      (node (ref "P11") (pin "1") (pinfunction "1_1") (pintype "passive"))
      (node (ref "P12") (pin "1") (pinfunction "1_1") (pintype "passive"))
      (node (ref "P2") (pin "5") (pinfunction "5_5") (pintype "passive"))
      (node (ref "P3") (pin "1") (pinfunction "1_1") (pintype "passive"))
      (node (ref "P4") (pin "2") (pinfunction "2_2") (pintype "passive"))
      (node (ref "P6") (pin "1") (pinfunction "1_1") (pintype "passive"))
      (node (ref "P7") (pin "1") (pinfunction "1_1") (pintype "passive"))
      (node (ref "P8") (pin "1") (pinfunction "1_1") (pintype "passive"))
      (node (ref "P9") (pin "1") (pinfunction "1_1") (pintype "passive"))
      (node (ref "Q1") (pin "3") (pinfunction "S_3") (pintype "passive"))
      (node (ref "Q10") (pin "3") (pinfunction "S_3") (pintype "passive"))
      (node (ref "Q2") (pin "3") (pinfunction "S_3") (pintype "passive"))
      (node (ref "Q3") (pin "3") (pinfunction "S_3") (pintype "passive"))
      (node (ref "Q7") (pin "3") (pinfunction "S_3") (pintype "passive"))
      (node (ref "Q8") (pin "3") (pinfunction "S_3") (pintype "passive"))
      (node (ref "R15") (pin "1") (pinfunction "1_1") (pintype "passive"))
      (node (ref "R17") (pin "2") (pinfunction "2_2") (pintype "passive"))
      (node (ref "R18") (pin "2") (pinfunction "2_2") (pintype "passive"))
      (node (ref "R19") (pin "2") (pinfunction "2_2") (pintype "passive"))
      (node (ref "R2") (pin "1") (pinfunction "1_1") (pintype "passive"))
      (node (ref "R23") (pin "1") (pinfunction "1_1") (pintype "passive"))
      (node (ref "R24") (pin "1") (pinfunction "1_1") (pintype "passive"))
      (node (ref "R26") (pin "1") (pinfunction "1_1") (pintype "passive"))
      (node (ref "R27") (pin "1") (pinfunction "1_1") (pintype "passive"))
      (node (ref "R4") (pin "1") (pinfunction "1_1") (pintype "passive"))
      (node (ref "R6") (pin "1") (pinfunction "1_1") (pintype "passive"))
      (node (ref "S1") (pin "3") (pinfunction "3_3") (pintype "passive"))
      (node (ref "S1") (pin "4") (pinfunction "4_4") (pintype "passive"))
      (node (ref "S2") (pin "3") (pinfunction "3_3") (pintype "passive"))
      (node (ref "S2") (pin "4") (pinfunction "4_4") (pintype "passive"))
      (node (ref "U1") (pin "2") (pinfunction "GND_2") (pintype "passive"))
      (node (ref "U10") (pin "3") (pinfunction "A_3") (pintype "power_in"))
      (node (ref "U12") (pin "23") (pinfunction "VSS_1_23") (pintype "power_in"))
      (node (ref "U12") (pin "35") (pinfunction "VSS_2_35") (pintype "power_in"))
      (node (ref "U12") (pin "44") (pinfunction "BOOT0_44") (pintype "input"))
      (node (ref "U12") (pin "47") (pinfunction "VSS_3_47") (pintype "power_in"))
      (node (ref "U12") (pin "8") (pinfunction "VSSA_8") (pintype "power_in"))
      (node (ref "U13") (pin "2") (pinfunction "GND_2") (pintype "passive"))
      (node (ref "U14") (pin "3") (pinfunction "VSS_3") (pintype "passive"))
      (node (ref "U15") (pin "3") (pinfunction "VSS_3") (pintype "passive"))
      (node (ref "U18") (pin "1") (pinfunction "GND_1") (pintype "passive"))
      (node (ref "U2") (pin "3") (pinfunction "VSS_3") (pintype "passive"))
      (node (ref "U4") (pin "2") (pinfunction "VSS_2") (pintype "passive"))
      (node (ref "U5") (pin "0") (pinfunction "GND_0") (pintype "passive"))
      (node (ref "U5") (pin "3") (pinfunction "GND_3") (pintype "passive"))
      (node (ref "U6") (pin "1") (pinfunction "CLKIN_1") (pintype "passive"))
      (node (ref "U6") (pin "18") (pinfunction "GND_18") (pintype "passive"))
      (node (ref "U6") (pin "9") (pinfunction "AD0_9") (pintype "passive"))
      (node (ref "U7") (pin "3") (pinfunction "VSS_3") (pintype "passive"))
      (node (ref "U8") (pin "1") (pinfunction "GND_1") (pintype "passive"))
      (node (ref "U8") (pin "9") (pinfunction "PGND_9") (pintype "passive"))
    )
    (net (code "42") (name "Net-(B1-G)") (class "Default")
      (node (ref "B1") (pin "2") (pinfunction "G_2") (pintype "passive"))
      (node (ref "R10") (pin "2") (pinfunction "2_2") (pintype "passive"))
    )
    (net (code "43") (name "Net-(C6-Pad2)") (class "Default")
      (node (ref "C6") (pin "2") (pinfunction "2_2") (pintype "passive"))
      (node (ref "R22") (pin "2") (pinfunction "2_2") (pintype "passive"))
    )
    (net (code "44") (name "Net-(C10-Pad2)") (class "Default")
      (node (ref "C10") (pin "2") (pinfunction "2_2") (pintype "passive"))
      (node (ref "R21") (pin "2") (pinfunction "2_2") (pintype "passive"))
    )
    (net (code "45") (name "Net-(D2-PadA)") (class "Default")
      (node (ref "D2") (pin "A") (pinfunction "A_A") (pintype "passive"))
      (node (ref "R5") (pin "1") (pinfunction "1_1") (pintype "passive"))
    )
    (net (code "46") (name "Net-(D3-K)") (class "Default")
      (node (ref "D3") (pin "2") (pinfunction "K_2") (pintype "passive"))
      (node (ref "R7") (pin "2") (pinfunction "2_2") (pintype "passive"))
    )
    (net (code "47") (name "Net-(D4-K)") (class "Default")
      (node (ref "D4") (pin "2") (pinfunction "K_2") (pintype "passive"))
      (node (ref "R8") (pin "2") (pinfunction "2_2") (pintype "passive"))
    )
    (net (code "48") (name "Net-(D5-K)") (class "Default")
      (node (ref "D5") (pin "2") (pinfunction "K_2") (pintype "passive"))
      (node (ref "R16") (pin "2") (pinfunction "2_2") (pintype "passive"))
    )
    (net (code "49") (name "Net-(D8-A)") (class "Default")
      (node (ref "D8") (pin "1") (pinfunction "A_1") (pintype "passive"))
      (node (ref "P1") (pin "4") (pinfunction "4_4") (pintype "passive"))
    )
    (net (code "50") (name "Net-(Q1-D)") (class "Default")
      (node (ref "Q1") (pin "1") (pinfunction "D_1") (pintype "passive"))
      (node (ref "R10") (pin "1") (pinfunction "1_1") (pintype "passive"))
    )
    (net (code "51") (name "Net-(Q7-D)") (class "Default")
      (node (ref "Q7") (pin "1") (pinfunction "D_1") (pintype "passive"))
      (node (ref "R16") (pin "1") (pinfunction "1_1") (pintype "passive"))
    )
    (net (code "52") (name "Net-(Q10-D)") (class "Default")
      (node (ref "Q10") (pin "1") (pinfunction "D_1") (pintype "passive"))
      (node (ref "U3") (pin "2") (pinfunction "K_2") (pintype "passive"))
      (node (ref "U9") (pin "2") (pinfunction "K_2") (pintype "passive"))
    )
    (net (code "53") (name "Net-(Q11-G)") (class "Default")
      (node (ref "Q11") (pin "2") (pinfunction "G_2") (pintype "passive"))
      (node (ref "R30") (pin "1") (pinfunction "1_1") (pintype "passive"))
    )
    (net (code "54") (name "Net-(Q11-S)") (class "Default")
      (node (ref "Q11") (pin "3") (pinfunction "S_3") (pintype "passive"))
      (node (ref "U5") (pin "24") (pinfunction "RTS_24") (pintype "passive"))
    )
    (net (code "55") (name "Net-(R9-Pad1)") (class "Default")
      (node (ref "R9") (pin "1") (pinfunction "1_1") (pintype "passive"))
      (node (ref "S1") (pin "1") (pinfunction "1_1") (pintype "passive"))
    )
    (net (code "56") (name "Net-(U3-A)") (class "Default")
      (node (ref "R13") (pin "2") (pinfunction "2_2") (pintype "passive"))
      (node (ref "U3") (pin "1") (pinfunction "A_1") (pintype "passive"))
    )
    (net (code "57") (name "Net-(U5-D+)") (class "Default")
      (node (ref "P2") (pin "3") (pinfunction "3_3") (pintype "passive"))
      (node (ref "U5") (pin "4") (pinfunction "D+_4") (pintype "passive"))
    )
    (net (code "58") (name "Net-(U5-D-)") (class "Default")
      (node (ref "P2") (pin "2") (pinfunction "2_2") (pintype "passive"))
      (node (ref "U5") (pin "5") (pinfunction "D-_5") (pintype "passive"))
    )
    (net (code "59") (name "Net-(U5-DTR)") (class "Default")
      (node (ref "C19") (pin "2") (pinfunction "2_2") (pintype "passive"))
      (node (ref "R29") (pin "1") (pinfunction "1_1") (pintype "passive"))
      (node (ref "U5") (pin "28") (pinfunction "DTR_28") (pintype "passive"))
    )
    (net (code "60") (name "Net-(U5-VDD)") (class "Default")
      (node (ref "C8") (pin "2") (pinfunction "2_2") (pintype "passive"))
      (node (ref "U5") (pin "6") (pinfunction "VDD_6") (pintype "passive"))
    )
    (net (code "61") (name "Net-(U6-CPOUT)") (class "Default")
      (node (ref "C18") (pin "1") (pinfunction "1_1") (pintype "passive"))
      (node (ref "U6") (pin "20") (pinfunction "CPOUT_20") (pintype "passive"))
    )
    (net (code "62") (name "Net-(U6-REGOUT)") (class "Default")
      (node (ref "C16") (pin "1") (pinfunction "1_1") (pintype "passive"))
      (node (ref "U6") (pin "10") (pinfunction "REGOUT_10") (pintype "passive"))
    )
    (net (code "63") (name "Net-(U8-AO1)") (class "Default")
      (node (ref "C6") (pin "1") (pinfunction "1_1") (pintype "passive"))
      (node (ref "M1") (pin "1") (pinfunction "1_1") (pintype "passive"))
      (node (ref "U8") (pin "7") (pinfunction "AO1_7") (pintype "passive"))
    )
    (net (code "64") (name "Net-(U8-AO2)") (class "Default")
      (node (ref "M1") (pin "2") (pinfunction "2_2") (pintype "passive"))
      (node (ref "R22") (pin "1") (pinfunction "1_1") (pintype "passive"))
      (node (ref "U8") (pin "8") (pinfunction "AO2_8") (pintype "passive"))
    )
    (net (code "65") (name "Net-(U8-BO1)") (class "Default")
      (node (ref "C10") (pin "1") (pinfunction "1_1") (pintype "passive"))
      (node (ref "M2") (pin "1") (pinfunction "1_1") (pintype "passive"))
      (node (ref "U8") (pin "11") (pinfunction "BO1_11") (pintype "passive"))
    )
    (net (code "66") (name "Net-(U8-BO2)") (class "Default")
      (node (ref "M2") (pin "2") (pinfunction "2_2") (pintype "passive"))
      (node (ref "R21") (pin "1") (pinfunction "1_1") (pintype "passive"))
      (node (ref "U8") (pin "10") (pinfunction "BO2_10") (pintype "passive"))
    )
    (net (code "67") (name "Net-(U8-VM)") (class "Default")
      (node (ref "R28") (pin "1") (pinfunction "1_1") (pintype "passive"))
      (node (ref "U8") (pin "6") (pinfunction "VM_6") (pintype "passive"))
    )
    (net (code "68") (name "Net-(U9-A)") (class "Default")
      (node (ref "R3") (pin "2") (pinfunction "2_2") (pintype "passive"))
      (node (ref "U9") (pin "1") (pinfunction "A_1") (pintype "passive"))
    )
    (net (code "69") (name "Net-(U12-OSC_IN{slash}PD0)") (class "Default")
      (node (ref "C7") (pin "2") (pintype "passive"))
      (node (ref "U12") (pin "5") (pinfunction "OSC_IN/PD0_5") (pintype "input"))
      (node (ref "Y1") (pin "1") (pinfunction "OSC1_1") (pintype "passive"))
    )
    (net (code "70") (name "Net-(U12-OSC_OUT{slash}PD1)") (class "Default")
      (node (ref "C11") (pin "2") (pintype "passive"))
      (node (ref "U12") (pin "6") (pinfunction "OSC_OUT/PD1_6") (pintype "output"))
      (node (ref "Y1") (pin "2") (pinfunction "OSC2_2") (pintype "passive"))
    )
    (net (code "71") (name "Net-(U13-CHRG)") (class "Default")
      (node (ref "D2") (pin "K") (pinfunction "K_K") (pintype "passive"))
      (node (ref "U13") (pin "1") (pinfunction "CHRG_1") (pintype "passive"))
    )
    (net (code "72") (name "Net-(U13-PROG)") (class "Default")
      (node (ref "R6") (pin "2") (pinfunction "2_2") (pintype "passive"))
      (node (ref "U13") (pin "6") (pinfunction "PROG_6") (pintype "passive"))
    )
    (net (code "73") (name "Net-(U13-STDBY)") (class "Default")
      (node (ref "D1") (pin "K") (pinfunction "K_K") (pintype "passive"))
      (node (ref "U13") (pin "5") (pinfunction "STDBY_5") (pintype "passive"))
    )
    (net (code "74") (name "Net-(U14-DO)") (class "Default")
      (node (ref "U14") (pin "2") (pinfunction "DO_2") (pintype "passive"))
      (node (ref "U15") (pin "4") (pinfunction "DI_4") (pintype "passive"))
      (node (ref "U2") (pin "4") (pinfunction "DI_4") (pintype "passive"))
    )
    (net (code "75") (name "unconnected-(P2-Pad4)") (class "Default")
      (node (ref "P2") (pin "4") (pinfunction "4_4") (pintype "passive"))
    )
    (net (code "76") (name "unconnected-(U2-DO-Pad2)") (class "Default")
      (node (ref "U2") (pin "2") (pinfunction "DO_2") (pintype "passive"))
    )
    (net (code "77") (name "unconnected-(U4-NC-Pad3)") (class "Default")
      (node (ref "U4") (pin "3") (pinfunction "NC_3") (pintype "passive"))
    )
    (net (code "78") (name "unconnected-(U4-NC-Pad4)") (class "Default")
      (node (ref "U4") (pin "4") (pinfunction "NC_4") (pintype "passive"))
    )
    (net (code "79") (name "unconnected-(U5-CTS-Pad23)") (class "Default")
      (node (ref "U5") (pin "23") (pinfunction "CTS_23") (pintype "passive"))
    )
    (net (code "80") (name "unconnected-(U5-DCD-Pad1)") (class "Default")
      (node (ref "U5") (pin "1") (pinfunction "DCD_1") (pintype "passive"))
    )
    (net (code "81") (name "unconnected-(U5-DSR-Pad27)") (class "Default")
      (node (ref "U5") (pin "27") (pinfunction "DSR_27") (pintype "passive"))
    )
    (net (code "82") (name "unconnected-(U5-NC-Pad10)") (class "Default")
      (node (ref "U5") (pin "10") (pinfunction "NC_10") (pintype "passive"))
    )
    (net (code "83") (name "unconnected-(U5-NC-Pad13)") (class "Default")
      (node (ref "U5") (pin "13") (pinfunction "NC_13") (pintype "passive"))
    )
    (net (code "84") (name "unconnected-(U5-NC-Pad14)") (class "Default")
      (node (ref "U5") (pin "14") (pinfunction "NC_14") (pintype "passive"))
    )
    (net (code "85") (name "unconnected-(U5-NC-Pad15)") (class "Default")
      (node (ref "U5") (pin "15") (pinfunction "NC_15") (pintype "passive"))
    )
    (net (code "86") (name "unconnected-(U5-NC-Pad16)") (class "Default")
      (node (ref "U5") (pin "16") (pinfunction "NC_16") (pintype "passive"))
    )
    (net (code "87") (name "unconnected-(U5-NC-Pad17)") (class "Default")
      (node (ref "U5") (pin "17") (pinfunction "NC_17") (pintype "passive"))
    )
    (net (code "88") (name "unconnected-(U5-NC-Pad18)") (class "Default")
      (node (ref "U5") (pin "18") (pinfunction "NC_18") (pintype "passive"))
    )
    (net (code "89") (name "unconnected-(U5-NC-Pad19)") (class "Default")
      (node (ref "U5") (pin "19") (pinfunction "NC_19") (pintype "passive"))
    )
    (net (code "90") (name "unconnected-(U5-NC-Pad20)") (class "Default")
      (node (ref "U5") (pin "20") (pinfunction "NC_20") (pintype "passive"))
    )
    (net (code "91") (name "unconnected-(U5-NC-Pad21)") (class "Default")
      (node (ref "U5") (pin "21") (pinfunction "NC_21") (pintype "passive"))
    )
    (net (code "92") (name "unconnected-(U5-NC-Pad22)") (class "Default")
      (node (ref "U5") (pin "22") (pinfunction "NC_22") (pintype "passive"))
    )
    (net (code "93") (name "unconnected-(U5-RI-Pad2)") (class "Default")
      (node (ref "U5") (pin "2") (pinfunction "RI_2") (pintype "passive"))
    )
    (net (code "94") (name "unconnected-(U5-RS~{T}-Pad9)") (class "Default")
      (node (ref "U5") (pin "9") (pinfunction "RS~{T}_9") (pintype "passive"))
    )
    (net (code "95") (name "unconnected-(U5-SUSPEND-Pad12)") (class "Default")
      (node (ref "U5") (pin "12") (pinfunction "SUSPEND_12") (pintype "passive"))
    )
    (net (code "96") (name "unconnected-(U5-SUSPEN~{D}-Pad11)") (class "Default")
      (node (ref "U5") (pin "11") (pinfunction "SUSPEN~{D}_11") (pintype "passive"))
    )
    (net (code "97") (name "unconnected-(U6-AUX_CL-Pad7)") (class "Default")
      (node (ref "U6") (pin "7") (pinfunction "AUX_CL_7") (pintype "passive"))
    )
    (net (code "98") (name "unconnected-(U6-AUX_DA-Pad6)") (class "Default")
      (node (ref "U6") (pin "6") (pinfunction "AUX_DA_6") (pintype "passive"))
    )
    (net (code "99") (name "unconnected-(U6-FSYNC-Pad11)") (class "Default")
      (node (ref "U6") (pin "11") (pinfunction "FSYNC_11") (pintype "passive"))
    )
    (net (code "100") (name "unconnected-(U6-INT-Pad12)") (class "Default")
      (node (ref "U6") (pin "12") (pinfunction "INT_12") (pintype "passive"))
    )
    (net (code "101") (name "unconnected-(U6-NC-2-Pad2)") (class "Default")
      (node (ref "U6") (pin "2") (pinfunction "NC-2_2") (pintype "passive"))
    )
    (net (code "102") (name "unconnected-(U6-NC-3-Pad3)") (class "Default")
      (node (ref "U6") (pin "3") (pinfunction "NC-3_3") (pintype "passive"))
    )
    (net (code "103") (name "unconnected-(U6-NC-4-Pad4)") (class "Default")
      (node (ref "U6") (pin "4") (pinfunction "NC-4_4") (pintype "passive"))
    )
    (net (code "104") (name "unconnected-(U6-NC-5-Pad5)") (class "Default")
      (node (ref "U6") (pin "5") (pinfunction "NC-5_5") (pintype "passive"))
    )
    (net (code "105") (name "unconnected-(U6-NC-14-Pad14)") (class "Default")
      (node (ref "U6") (pin "14") (pinfunction "NC-14_14") (pintype "passive"))
    )
    (net (code "106") (name "unconnected-(U6-NC-15-Pad15)") (class "Default")
      (node (ref "U6") (pin "15") (pinfunction "NC-15_15") (pintype "passive"))
    )
    (net (code "107") (name "unconnected-(U6-NC-16-Pad16)") (class "Default")
      (node (ref "U6") (pin "16") (pinfunction "NC-16_16") (pintype "passive"))
    )
    (net (code "108") (name "unconnected-(U6-NC-17-Pad17)") (class "Default")
      (node (ref "U6") (pin "17") (pinfunction "NC-17_17") (pintype "passive"))
    )
    (net (code "109") (name "unconnected-(U6-PWR_PAD-Pad25)") (class "Default")
      (node (ref "U6") (pin "25") (pinfunction "PWR_PAD_25") (pintype "passive"))
    )
    (net (code "110") (name "unconnected-(U6-RESV-19-Pad19)") (class "Default")
      (node (ref "U6") (pin "19") (pinfunction "RESV-19_19") (pintype "passive"))
    )
    (net (code "111") (name "unconnected-(U6-RESV-21-Pad21)") (class "Default")
      (node (ref "U6") (pin "21") (pinfunction "RESV-21_21") (pintype "passive"))
    )
    (net (code "112") (name "unconnected-(U6-RESV-22-Pad22)") (class "Default")
      (node (ref "U6") (pin "22") (pinfunction "RESV-22_22") (pintype "passive"))
    )
    (net (code "113") (name "unconnected-(U7-DO-Pad2)") (class "Default")
      (node (ref "U7") (pin "2") (pinfunction "DO_2") (pintype "passive"))
    )
    (net (code "114") (name "unconnected-(U12-PA8-Pad29)") (class "Default")
      (node (ref "U12") (pin "29") (pinfunction "PA8_29") (pintype "bidirectional"))
    )
    (net (code "115") (name "unconnected-(U12-PB2{slash}BOOT1-Pad20)") (class "Default")
      (node (ref "U12") (pin "20") (pinfunction "PB2/BOOT1_20") (pintype "bidirectional"))
    )
    (net (code "116") (name "unconnected-(U12-PB10-Pad21)") (class "Default")
      (node (ref "U12") (pin "21") (pinfunction "PB10_21") (pintype "bidirectional"))
    )
    (net (code "117") (name "unconnected-(U12-PB14-Pad27)") (class "Default")
      (node (ref "U12") (pin "27") (pinfunction "PB14_27") (pintype "bidirectional"))
    )
    (net (code "118") (name "unconnected-(U15-DO-Pad2)") (class "Default")
      (node (ref "U15") (pin "2") (pinfunction "DO_2") (pintype "passive"))
    )
  )
)
